# MICS-2614_O3_Sensor_Breakout.net
KiCad netlist of a schematic drawn in EAGLE
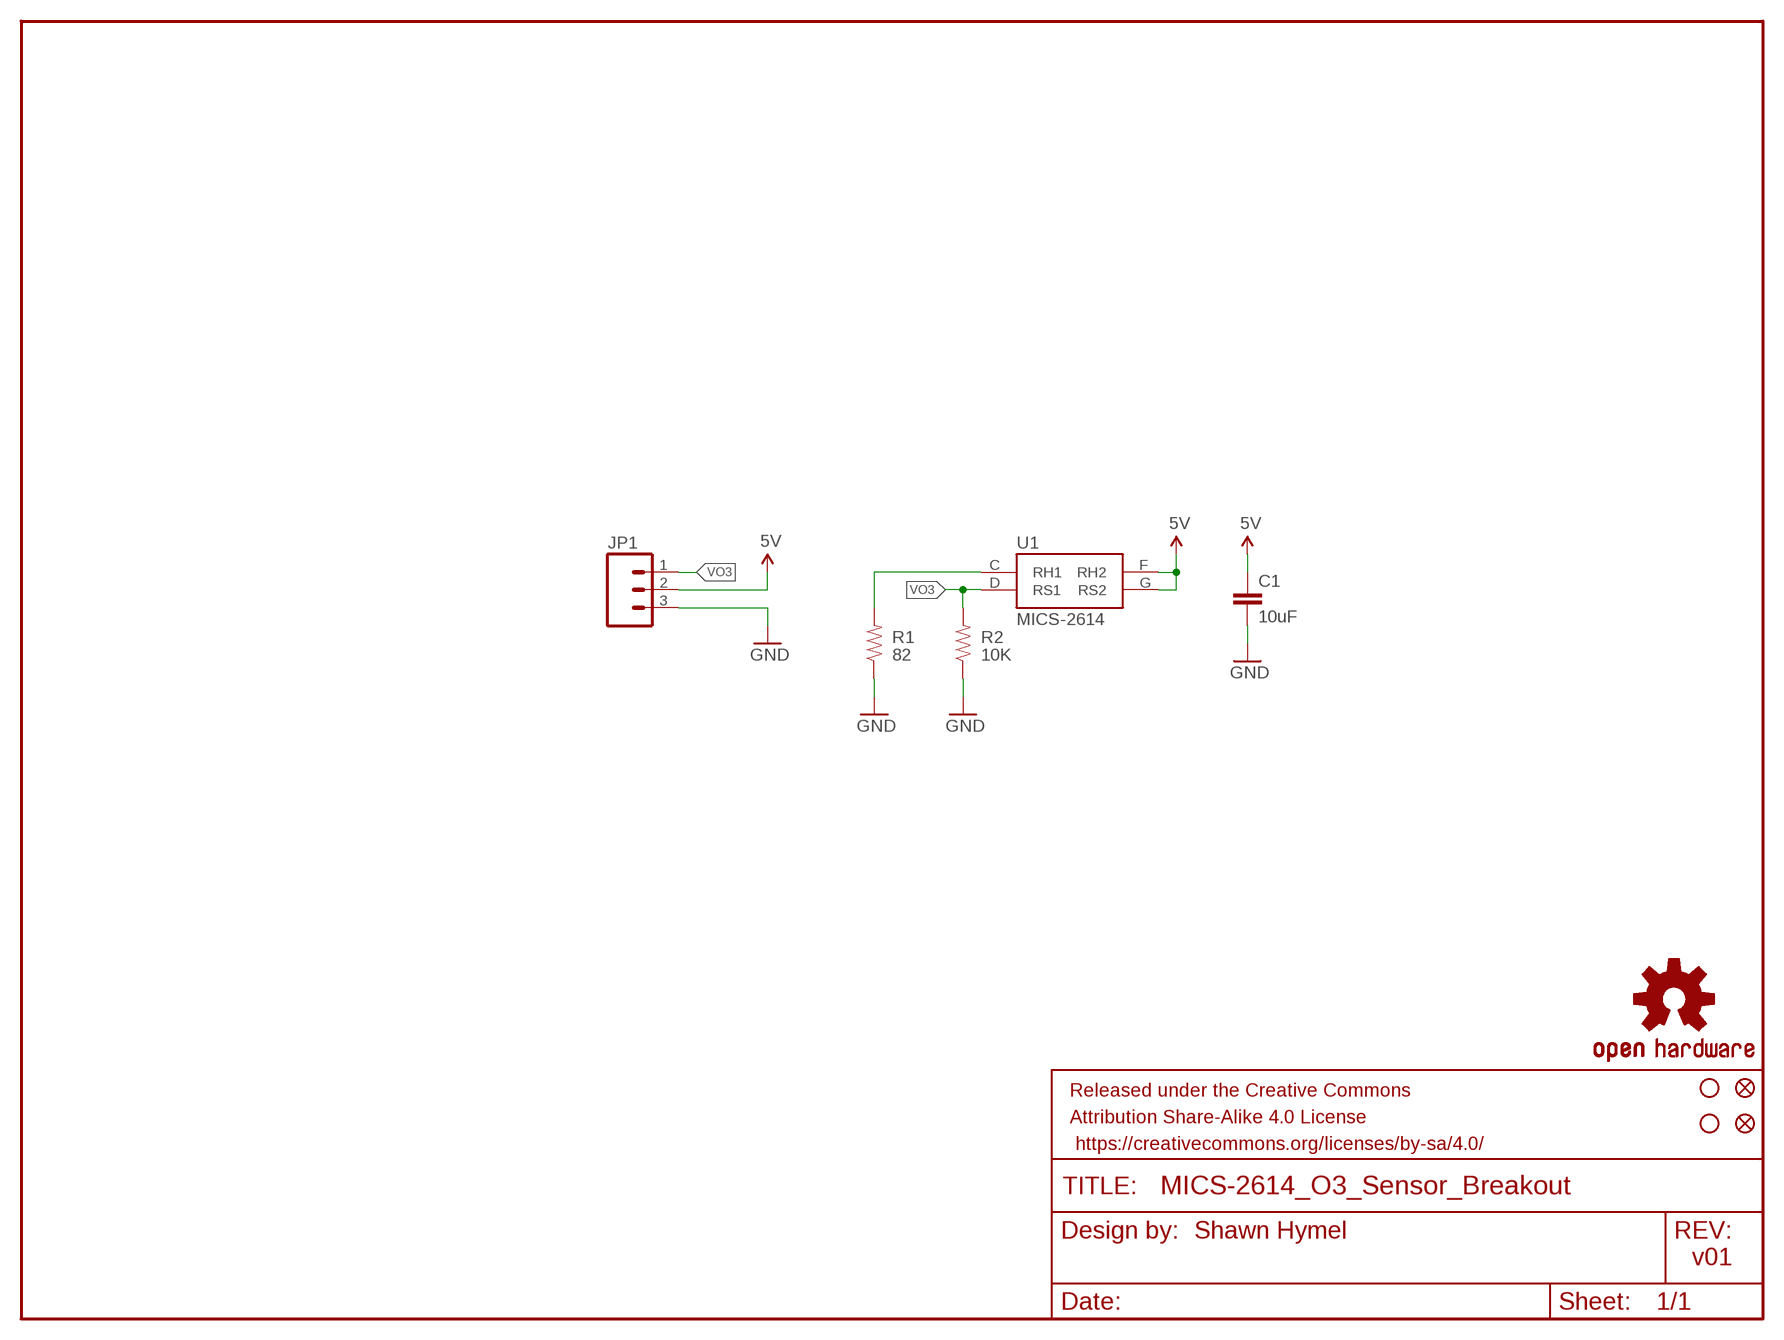
[diagram p0: schematic, sheet 1]

(export (version "E")
  (design (tool "Eeschema 10.0.6"))
  (components
    (comp (ref "C1")
      (value "10uF")
      (footprint "eagle-import:0805")
      (libsource (lib "eagle-import") (part "CAP0805"))
    )
    (comp (ref "FID1")
      (value "FIDUCIAL1X2")
      (footprint "eagle-import:FIDUCIAL-1X2")
      (libsource (lib "eagle-import") (part "FIDUCIAL1X2"))
    )
    (comp (ref "FID2")
      (value "FIDUCIAL1X2")
      (footprint "eagle-import:FIDUCIAL-1X2")
      (libsource (lib "eagle-import") (part "FIDUCIAL1X2"))
    )
    (comp (ref "FRAME1")
      (value "FRAME-LETTER")
      (footprint "eagle-import:CREATIVE_COMMONS")
      (libsource (lib "eagle-import") (part "FRAME-LETTER"))
    )
    (comp (ref "JP1")
      (value "M03LOCK")
      (footprint "eagle-import:1X03_LOCK")
      (libsource (lib "eagle-import") (part "M03LOCK"))
    )
    (comp (ref "LOGO1")
      (value "OSHW-LOGOS")
      (footprint "eagle-import:OSHW-LOGO-S")
      (libsource (lib "eagle-import") (part "OSHW-LOGOS"))
    )
    (comp (ref "R1")
      (value "82")
      (footprint "eagle-import:0805")
      (libsource (lib "eagle-import") (part "RESISTOR0805-RES"))
    )
    (comp (ref "R2")
      (value "10K")
      (footprint "eagle-import:0603-RES")
      (libsource (lib "eagle-import") (part "10KOHM1/10W1%(0603)0603"))
    )
    (comp (ref "STANDOFF3")
      (value "STAND-OFF")
      (footprint "eagle-import:STAND-OFF")
      (libsource (lib "eagle-import") (part "STAND-OFF"))
    )
    (comp (ref "STANDOFF5")
      (value "STAND-OFF")
      (footprint "eagle-import:STAND-OFF")
      (libsource (lib "eagle-import") (part "STAND-OFF"))
    )
    (comp (ref "U1")
      (value "MICS-2614")
      (footprint "eagle-import:MICS_10-SMD")
      (libsource (lib "eagle-import") (part "MICS-2614"))
    )
  )
  (nets
    (net (code "1") (name "5V") (class "Default")
      (node (ref "C1") (pin "1") (pinfunction "1_1") (pintype "passive"))
      (node (ref "JP1") (pin "2") (pinfunction "2_2") (pintype "passive"))
      (node (ref "U1") (pin "F") (pinfunction "RH2_F") (pintype "bidirectional"))
      (node (ref "U1") (pin "G") (pinfunction "RS2_G") (pintype "bidirectional"))
    )
    (net (code "2") (name "GND") (class "Default")
      (node (ref "C1") (pin "2") (pinfunction "2_2") (pintype "passive"))
      (node (ref "JP1") (pin "3") (pinfunction "3_3") (pintype "passive"))
      (node (ref "R1") (pin "1") (pinfunction "1_1") (pintype "passive"))
      (node (ref "R2") (pin "1") (pinfunction "1_1") (pintype "passive"))
    )
    (net (code "3") (name "Net-(U1-RH1)") (class "Default")
      (node (ref "R1") (pin "2") (pinfunction "2_2") (pintype "passive"))
      (node (ref "U1") (pin "C") (pinfunction "RH1_C") (pintype "bidirectional"))
    )
    (net (code "4") (name "VO3") (class "Default")
      (node (ref "JP1") (pin "1") (pinfunction "1_1") (pintype "passive"))
      (node (ref "R2") (pin "2") (pinfunction "2_2") (pintype "passive"))
      (node (ref "U1") (pin "D") (pinfunction "RS1_D") (pintype "bidirectional"))
    )
  )
)
